# CurrentSensor.net
KiCad netlist of a schematic drawn in Altium Designer
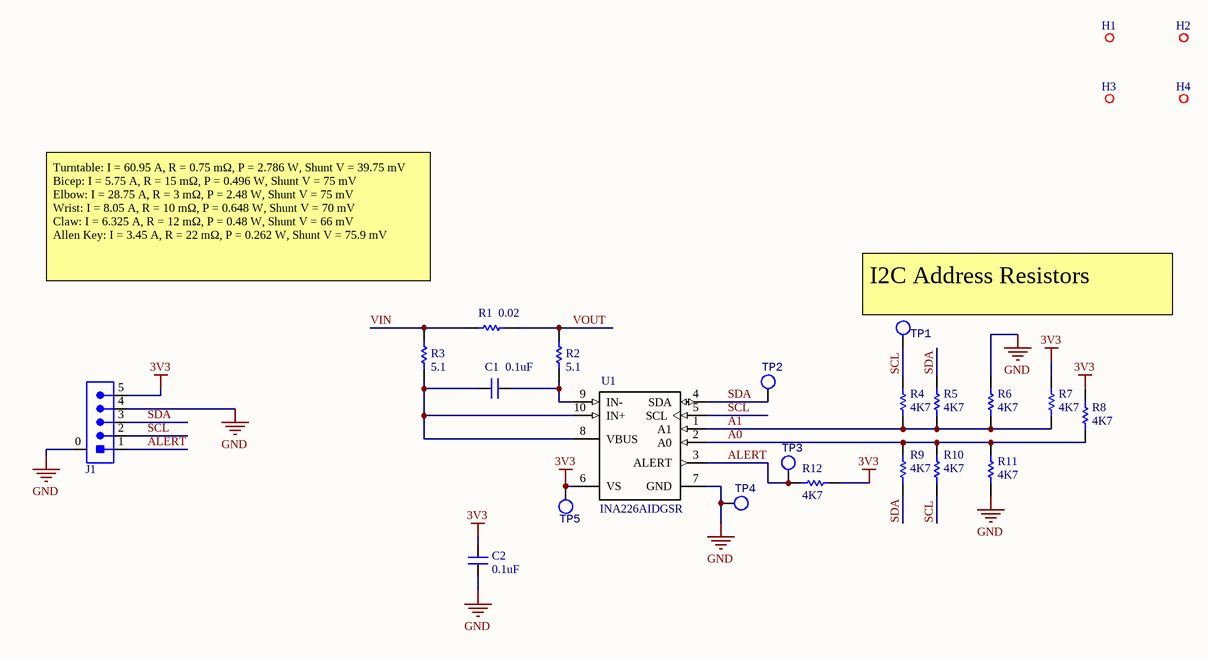
[diagram p0: CurrentSensor.SchDoc]

(export (version "E")
  (design (tool "Eeschema 10.0.6"))
  (components
    (comp (ref "C1")
      (value "0.1uF")
      (footprint "CAPC2012X140N")
      (description "CAP CER 0.1UF 50V X7R 0805")
      (fields (field (name "TOLERANCE") "10%") (field (name "Comment") "CAP_0.1uF_50V_0805"))
      (libsource (lib "UWRT_Schematic_Library_2020") (part "CAP_0.1uF_50V_0805"))
    )
    (comp (ref "C2")
      (value "0.1uF")
      (footprint "CAPC2012X140N")
      (description "CAP CER 0.1UF 50V X7R 0805")
      (fields (field (name "TOLERANCE") "10%") (field (name "Comment") "CAP_0.1uF_50V_0805"))
      (libsource (lib "UWRT_Schematic_Library_2020") (part "CAP_0.1uF_50V_0805"))
    )
    (comp (ref "H1")
      (value "MOUNTING_HOLES")
      (footprint "MOUNTING_HOLE")
      (description "6cm x 6cm")
      (libsource (lib "UWRT_Schematic_Library_2020") (part "MOUNTING_HOLES"))
    )
    (comp (ref "H2")
      (value "MOUNTING_HOLES")
      (footprint "MOUNTING_HOLE")
      (description "6cm x 6cm")
      (libsource (lib "UWRT_Schematic_Library_2020") (part "MOUNTING_HOLES"))
    )
    (comp (ref "H3")
      (value "MOUNTING_HOLES")
      (footprint "MOUNTING_HOLE")
      (description "6cm x 6cm")
      (libsource (lib "UWRT_Schematic_Library_2020") (part "MOUNTING_HOLES"))
    )
    (comp (ref "H4")
      (value "MOUNTING_HOLES")
      (footprint "MOUNTING_HOLE")
      (description "6cm x 6cm")
      (libsource (lib "UWRT_Schematic_Library_2020") (part "MOUNTING_HOLES"))
    )
    (comp (ref "J1")
      (value "CON_5M_SM4")
      (footprint "JST-B5B-SM4-TB")
      (description "CONN HEADER SMD 5POS 2MM")
      (fields
        (field (name "MANUFACTURER") "JST")
        (field (name "MANUFACTURER PART NUMBER") "B5B-PH-SM4-TB(LF)(SN)")
      )
      (libsource (lib "UWRT_Schematic_Library_2020") (part "CON_5M_SM4"))
    )
    (comp (ref "R1")
      (value "0.02")
      (footprint "RESC6532X75N")
      (description "RES 0.02 OHM 1% 3W 2512")
      (fields (field (name "Comment") "RES_20m_2512"))
      (libsource (lib "UWRT_Schematic_Library_2020") (part "RES_20m_2512"))
    )
    (comp (ref "R2")
      (value "5.1")
      (footprint "RESC2013X70X40LL20T20")
      (description "RES SMD 5.1 OHM 5% 1/8W 0805")
      (fields (field (name "PART NUMBER") "ERJ-6GEYJ5R1V") (field (name "MANUFACTURER") "Panasonic"))
      (libsource (lib "UWRT_Schematic_Library_2020") (part "RES_5.1_0805"))
    )
    (comp (ref "R3")
      (value "5.1")
      (footprint "RESC2013X70X40LL20T20")
      (description "RES SMD 5.1 OHM 5% 1/8W 0805")
      (fields (field (name "PART NUMBER") "ERJ-6GEYJ5R1V") (field (name "MANUFACTURER") "Panasonic"))
      (libsource (lib "UWRT_Schematic_Library_2020") (part "RES_5.1_0805"))
    )
    (comp (ref "R4")
      (value "4K7")
      (footprint "RESC2012X60N")
      (description "RES SMD 4.7K OHM 5% 1/8W 0805")
      (fields (field (name "TOLERANCE") "5%") (field (name "Comment") "RES_4K7_0805"))
      (libsource (lib "UWRT_Schematic_Library_2020") (part "RES_4K7_0805"))
    )
    (comp (ref "R5")
      (value "4K7")
      (footprint "RESC2012X60N")
      (description "RES SMD 4.7K OHM 5% 1/8W 0805")
      (fields (field (name "TOLERANCE") "5%") (field (name "Comment") "RES_4K7_0805"))
      (libsource (lib "UWRT_Schematic_Library_2020") (part "RES_4K7_0805"))
    )
    (comp (ref "R6")
      (value "4K7")
      (footprint "RESC2012X60N")
      (description "RES SMD 4.7K OHM 5% 1/8W 0805")
      (fields (field (name "TOLERANCE") "5%") (field (name "Comment") "RES_4K7_0805"))
      (libsource (lib "UWRT_Schematic_Library_2020") (part "RES_4K7_0805"))
    )
    (comp (ref "R7")
      (value "4K7")
      (footprint "RESC2012X60N")
      (description "RES SMD 4.7K OHM 5% 1/8W 0805")
      (fields (field (name "TOLERANCE") "5%") (field (name "Comment") "RES_4K7_0805"))
      (libsource (lib "UWRT_Schematic_Library_2020") (part "RES_4K7_0805"))
    )
    (comp (ref "R8")
      (value "4K7")
      (footprint "RESC2012X60N")
      (description "RES SMD 4.7K OHM 5% 1/8W 0805")
      (fields (field (name "TOLERANCE") "5%") (field (name "Comment") "RES_4K7_0805"))
      (libsource (lib "UWRT_Schematic_Library_2020") (part "RES_4K7_0805"))
    )
    (comp (ref "R9")
      (value "4K7")
      (footprint "RESC2012X60N")
      (description "RES SMD 4.7K OHM 5% 1/8W 0805")
      (fields (field (name "TOLERANCE") "5%") (field (name "Comment") "RES_4K7_0805"))
      (libsource (lib "UWRT_Schematic_Library_2020") (part "RES_4K7_0805"))
    )
    (comp (ref "R10")
      (value "4K7")
      (footprint "RESC2012X60N")
      (description "RES SMD 4.7K OHM 5% 1/8W 0805")
      (fields (field (name "TOLERANCE") "5%") (field (name "Comment") "RES_4K7_0805"))
      (libsource (lib "UWRT_Schematic_Library_2020") (part "RES_4K7_0805"))
    )
    (comp (ref "R11")
      (value "4K7")
      (footprint "RESC2012X60N")
      (description "RES SMD 4.7K OHM 5% 1/8W 0805")
      (fields (field (name "TOLERANCE") "5%") (field (name "Comment") "RES_4K7_0805"))
      (libsource (lib "UWRT_Schematic_Library_2020") (part "RES_4K7_0805"))
    )
    (comp (ref "R12")
      (value "4K7")
      (footprint "RESC2012X60N")
      (description "RES SMD 4.7K OHM 5% 1/8W 0805")
      (fields (field (name "TOLERANCE") "5%") (field (name "Comment") "RES_4K7_0805"))
      (libsource (lib "UWRT_Schematic_Library_2020") (part "RES_4K7_0805"))
    )
    (comp (ref "TP1")
      (value "TESTPOINT_LOOP")
      (footprint "TESTPOINT_LOOP")
      (description "Loop testpoint through-hole pad")
      (fields (field (name "MANUFACTURER") "Keystone Electronics"))
      (libsource (lib "UWRT_Schematic_Library_2020") (part "TESTPOINT_LOOP"))
    )
    (comp (ref "TP2")
      (value "TESTPOINT_LOOP")
      (footprint "TESTPOINT_LOOP")
      (description "Loop testpoint through-hole pad")
      (fields (field (name "MANUFACTURER") "Keystone Electronics"))
      (libsource (lib "UWRT_Schematic_Library_2020") (part "TESTPOINT_LOOP"))
    )
    (comp (ref "TP3")
      (value "TESTPOINT_LOOP")
      (footprint "TESTPOINT_LOOP")
      (description "Loop testpoint through-hole pad")
      (fields (field (name "MANUFACTURER") "Keystone Electronics"))
      (libsource (lib "UWRT_Schematic_Library_2020") (part "TESTPOINT_LOOP"))
    )
    (comp (ref "TP4")
      (value "TESTPOINT_LOOP")
      (footprint "TESTPOINT_LOOP")
      (description "Loop testpoint through-hole pad")
      (fields (field (name "MANUFACTURER") "Keystone Electronics"))
      (libsource (lib "UWRT_Schematic_Library_2020") (part "TESTPOINT_LOOP"))
    )
    (comp (ref "TP5")
      (value "TESTPOINT_LOOP")
      (footprint "TESTPOINT_LOOP")
      (description "Loop testpoint through-hole pad")
      (fields (field (name "MANUFACTURER") "Keystone Electronics"))
      (libsource (lib "UWRT_Schematic_Library_2020") (part "TESTPOINT_LOOP"))
    )
    (comp (ref "U1")
      (value "INA226AIDGSR")
      (footprint "INA226AIDGSR")
      (description "IC MONITOR PWR/CURR BIDIR 10MSOP")
      (fields (field (name "MF") "Texas Instruments"))
      (libsource (lib "UWRT_Schematic_Library_2020") (part "INA226AIDGSR"))
    )
  )
  (nets
    (net (code "1") (name "/A0") (class "Default")
      (node (ref "R10") (pin "1") (pinfunction "1_1") (pintype "passive"))
      (node (ref "R11") (pin "1") (pinfunction "1_1") (pintype "passive"))
      (node (ref "R8") (pin "1") (pinfunction "1_1") (pintype "passive"))
      (node (ref "R9") (pin "1") (pinfunction "1_1") (pintype "passive"))
      (node (ref "U1") (pin "2") (pinfunction "A0_2") (pintype "input"))
    )
    (net (code "2") (name "/A1") (class "Default")
      (node (ref "R4") (pin "1") (pinfunction "1_1") (pintype "passive"))
      (node (ref "R5") (pin "1") (pinfunction "1_1") (pintype "passive"))
      (node (ref "R6") (pin "1") (pinfunction "1_1") (pintype "passive"))
      (node (ref "R7") (pin "1") (pinfunction "1_1") (pintype "passive"))
      (node (ref "U1") (pin "1") (pinfunction "A1_1") (pintype "input"))
    )
    (net (code "3") (name "/ALERT") (class "Default")
      (node (ref "J1") (pin "1") (pinfunction "1_1") (pintype "passive"))
      (node (ref "R12") (pin "1") (pinfunction "1_1") (pintype "passive"))
      (node (ref "TP3") (pin "1") (pintype "passive"))
      (node (ref "U1") (pin "3") (pinfunction "ALERT_3") (pintype "output"))
    )
    (net (code "4") (name "/SCL") (class "Default")
      (node (ref "J1") (pin "2") (pinfunction "2_2") (pintype "passive"))
      (node (ref "R10") (pin "2") (pinfunction "2_2") (pintype "passive"))
      (node (ref "R4") (pin "2") (pinfunction "2_2") (pintype "passive"))
      (node (ref "TP1") (pin "1") (pintype "passive"))
      (node (ref "U1") (pin "5") (pinfunction "SCL_5") (pintype "input"))
    )
    (net (code "5") (name "/SDA") (class "Default")
      (node (ref "J1") (pin "3") (pinfunction "3_3") (pintype "passive"))
      (node (ref "R5") (pin "2") (pinfunction "2_2") (pintype "passive"))
      (node (ref "R9") (pin "2") (pinfunction "2_2") (pintype "passive"))
      (node (ref "TP2") (pin "1") (pintype "passive"))
      (node (ref "U1") (pin "4") (pinfunction "SDA_4") (pintype "bidirectional"))
    )
    (net (code "6") (name "/VIN") (class "Default")
      (node (ref "R1") (pin "1") (pinfunction "1_1") (pintype "passive"))
      (node (ref "R3") (pin "2") (pinfunction "2_2") (pintype "passive"))
    )
    (net (code "7") (name "/VOUT") (class "Default")
      (node (ref "R1") (pin "2") (pinfunction "2_2") (pintype "passive"))
      (node (ref "R2") (pin "2") (pinfunction "2_2") (pintype "passive"))
    )
    (net (code "8") (name "3V3") (class "Default")
      (node (ref "C2") (pin "2") (pinfunction "2_2") (pintype "passive"))
      (node (ref "J1") (pin "5") (pinfunction "5_5") (pintype "passive"))
      (node (ref "R12") (pin "2") (pinfunction "2_2") (pintype "passive"))
      (node (ref "R7") (pin "2") (pinfunction "2_2") (pintype "passive"))
      (node (ref "R8") (pin "2") (pinfunction "2_2") (pintype "passive"))
      (node (ref "TP5") (pin "1") (pintype "passive"))
      (node (ref "U1") (pin "6") (pinfunction "VS_6") (pintype "power_in"))
    )
    (net (code "9") (name "GND") (class "Default")
      (node (ref "C2") (pin "1") (pinfunction "1_1") (pintype "passive"))
      (node (ref "J1") (pin "0") (pinfunction "0_0") (pintype "passive"))
      (node (ref "J1") (pin "4") (pinfunction "4_4") (pintype "passive"))
      (node (ref "R11") (pin "2") (pinfunction "2_2") (pintype "passive"))
      (node (ref "R6") (pin "2") (pinfunction "2_2") (pintype "passive"))
      (node (ref "TP4") (pin "1") (pintype "passive"))
      (node (ref "U1") (pin "7") (pinfunction "GND_7") (pintype "power_in"))
    )
    (net (code "10") (name "Net-(U1-IN+)") (class "Default")
      (node (ref "C1") (pin "1") (pinfunction "1_1") (pintype "passive"))
      (node (ref "R3") (pin "1") (pinfunction "1_1") (pintype "passive"))
      (node (ref "U1") (pin "10") (pinfunction "IN+_10") (pintype "input"))
      (node (ref "U1") (pin "8") (pinfunction "VBUS_8") (pintype "power_in"))
    )
    (net (code "11") (name "Net-(U1-IN-)") (class "Default")
      (node (ref "C1") (pin "2") (pinfunction "2_2") (pintype "passive"))
      (node (ref "R2") (pin "1") (pinfunction "1_1") (pintype "passive"))
      (node (ref "U1") (pin "9") (pinfunction "IN-_9") (pintype "input"))
    )
  )
)
